# carte_pami26.net
KiCad netlist of a schematic drawn in Altium Designer
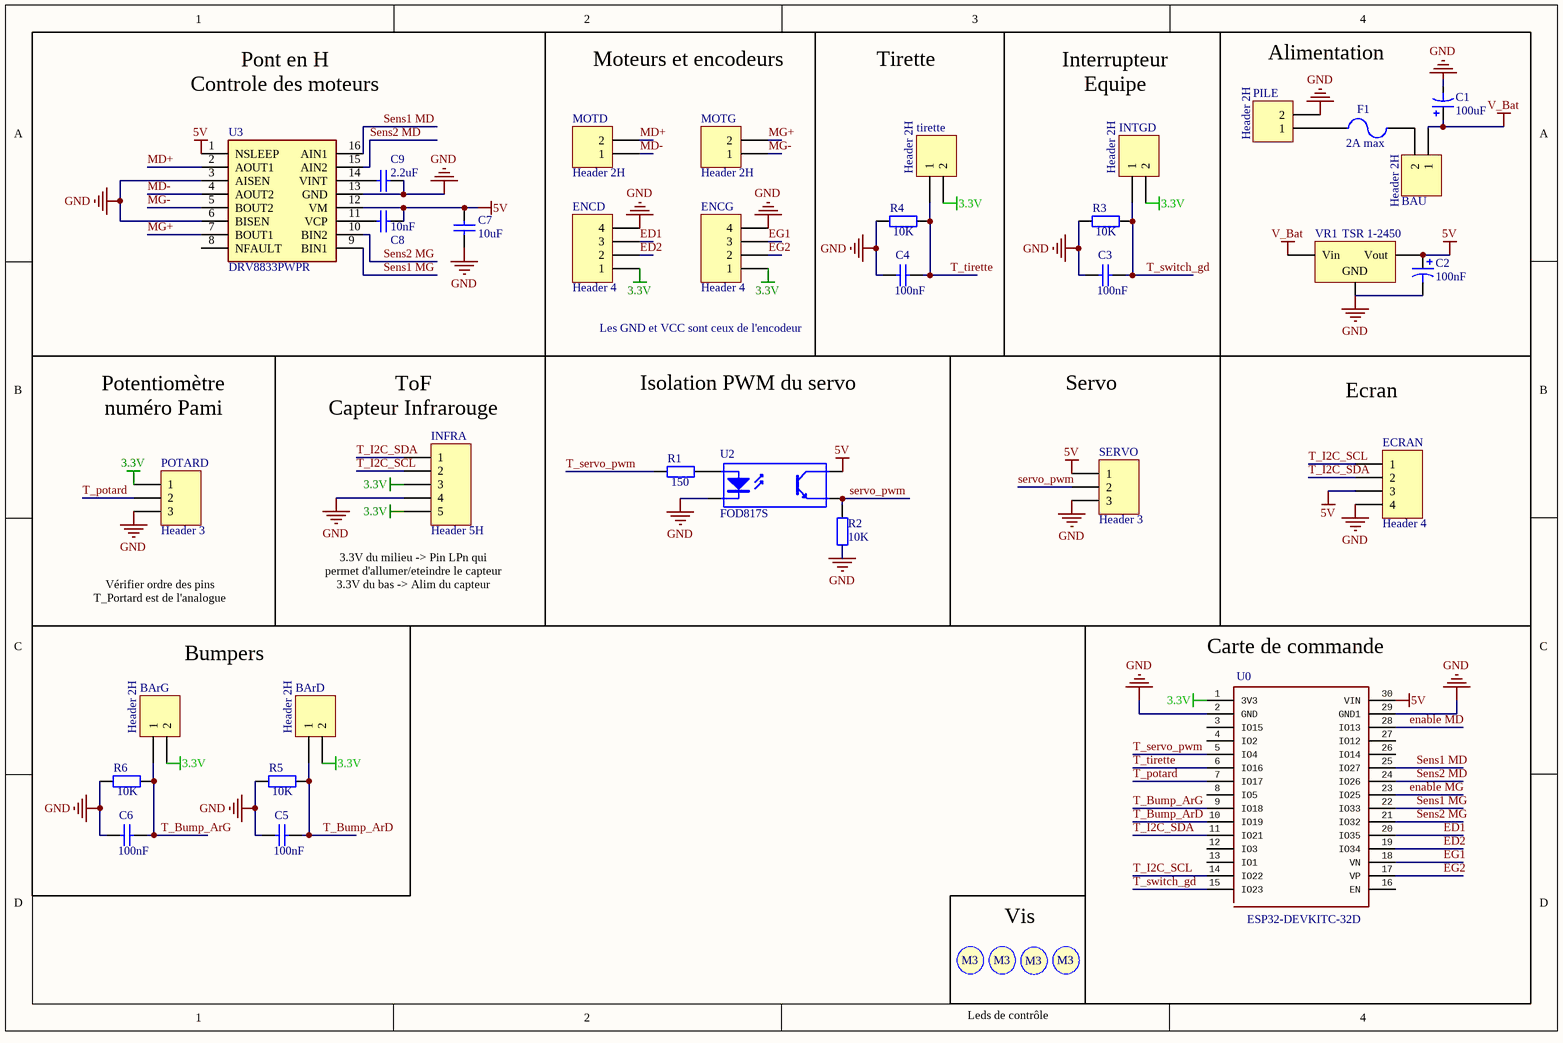
[diagram p0: carte_pami26.SchDoc]

(export (version "E")
  (design (tool "Eeschema 10.0.6"))
  (components
    (comp (ref "BArD")
      (value "Header 2H")
      (footprint "JST_B2B-XH-A_(LF)(SN)")
      (description "Header, 2-Pin, Right Angle")
      (fields (field (name "PUBLISHER") "Altium Limited"))
      (libsource (lib "Miscellaneous Connectors") (part "Header 2H"))
    )
    (comp (ref "BArG")
      (value "Header 2H")
      (footprint "JST_B2B-XH-A_(LF)(SN)")
      (description "Header, 2-Pin, Right Angle")
      (fields (field (name "PUBLISHER") "Altium Limited"))
      (libsource (lib "Miscellaneous Connectors") (part "Header 2H"))
    )
    (comp (ref "BAU")
      (value "Header 2H")
      (footprint "JST_B2B-XH-A_(LF)(SN)")
      (description "Header, 2-Pin, Right Angle")
      (fields (field (name "PUBLISHER") "Altium Limited"))
      (libsource (lib "") (part "Header 2H_1"))
    )
    (comp (ref "C1")
      (value "100uF")
      (footprint "Condensateur")
      (description "Polarized Capacitor (Radial)")
      (fields (field (name "Comment") "35V") (field (name "PUBLISHER") "Altium Limited"))
      (libsource (lib "Miscellaneous Devices") (part "Cap Pol1"))
    )
    (comp (ref "C2")
      (value "100nF")
      (footprint "Condensateur")
      (description "Polarized Capacitor (Radial)")
      (fields (field (name "Comment") "35V") (field (name "PUBLISHER") "Altium Limited"))
      (libsource (lib "Miscellaneous Devices") (part "Cap Pol1"))
    )
    (comp (ref "C3")
      (value "100nF")
      (footprint "Capacitor 1206")
      (description "Capacitor")
      (fields (field (name "Comment") "Cap") (field (name "PUBLISHER") "Altium Limited"))
      (libsource (lib "Miscellaneous Devices") (part "Cap"))
    )
    (comp (ref "C4")
      (value "100nF")
      (footprint "Capacitor 1206")
      (description "Capacitor")
      (fields (field (name "Comment") "Cap") (field (name "PUBLISHER") "Altium Limited"))
      (libsource (lib "Miscellaneous Devices") (part "Cap"))
    )
    (comp (ref "C5")
      (value "100nF")
      (footprint "Capacitor 1206")
      (description "Capacitor")
      (fields (field (name "Comment") "Cap") (field (name "PUBLISHER") "Altium Limited"))
      (libsource (lib "Miscellaneous Devices") (part "Cap"))
    )
    (comp (ref "C6")
      (value "100nF")
      (footprint "Capacitor 1206")
      (description "Capacitor")
      (fields (field (name "Comment") "Cap") (field (name "PUBLISHER") "Altium Limited"))
      (libsource (lib "Miscellaneous Devices") (part "Cap"))
    )
    (comp (ref "C7")
      (value "10uF")
      (footprint "Capacitor 1206")
      (description "Capacitor")
      (fields (field (name "Comment") "Cap") (field (name "PUBLISHER") "Altium Limited"))
      (libsource (lib "Miscellaneous Devices") (part "Cap"))
    )
    (comp (ref "C8")
      (value "10nF")
      (footprint "Capacitor 1206")
      (description "Capacitor")
      (fields (field (name "Comment") "Cap") (field (name "PUBLISHER") "Altium Limited"))
      (libsource (lib "Miscellaneous Devices") (part "Cap"))
    )
    (comp (ref "C9")
      (value "2.2uF")
      (footprint "Capacitor 1206")
      (description "Capacitor")
      (fields (field (name "Comment") "Cap") (field (name "PUBLISHER") "Altium Limited"))
      (libsource (lib "Miscellaneous Devices") (part "Cap"))
    )
    (comp (ref "ECRAN")
      (value "Header 4")
      (footprint "B4BXHALFSN")
      (description "Header, 4-Pin")
      (fields (field (name "PUBLISHER") "Altium Limited"))
      (libsource (lib "") (part "Header 4_1"))
    )
    (comp (ref "ENCD")
      (value "Header 4")
      (footprint "B4BXHALFSN")
      (description "Header, 4-Pin")
      (fields (field (name "PUBLISHER") "Altium Limited"))
      (libsource (lib "Miscellaneous Connectors") (part "Header 4"))
    )
    (comp (ref "ENCG")
      (value "Header 4")
      (footprint "B4BXHALFSN")
      (description "Header, 4-Pin")
      (fields (field (name "PUBLISHER") "Altium Limited"))
      (libsource (lib "Miscellaneous Connectors") (part "Header 4"))
    )
    (comp (ref "F1")
      (value "2A max")
      (footprint "Fuse")
      (description "Main Fuse")
      (fields (field (name "PUBLISHER") "Altium Limited"))
      (libsource (lib "Miscellaneous Devices") (part "Fuse 2"))
    )
    (comp (ref "INFRA")
      (value "Header 5H")
      (footprint "B5BXHAMLFSN")
      (description "Header, 5-Pin, Right Angle")
      (fields (field (name "PUBLISHER") "Altium Limited"))
      (libsource (lib "Miscellaneous Connectors") (part "Header 5H"))
    )
    (comp (ref "INTGD")
      (value "Header 2H")
      (footprint "JST_B2B-XH-A_(LF)(SN)")
      (description "Header, 2-Pin, Right Angle")
      (fields (field (name "PUBLISHER") "Altium Limited"))
      (libsource (lib "Miscellaneous Connectors") (part "Header 2H"))
    )
    (comp (ref "MOTD")
      (value "Header 2H")
      (footprint "JST_B2B-XH-A_(LF)(SN)")
      (description "Header, 2-Pin, Right Angle")
      (fields (field (name "PUBLISHER") "Altium Limited"))
      (libsource (lib "") (part "Header 2H_2"))
    )
    (comp (ref "MOTG")
      (value "Header 2H")
      (footprint "JST_B2B-XH-A_(LF)(SN)")
      (description "Header, 2-Pin, Right Angle")
      (fields (field (name "PUBLISHER") "Altium Limited"))
      (libsource (lib "") (part "Header 2H_2"))
    )
    (comp (ref "PILE")
      (value "Header 2H")
      (footprint "JST_B2B-XH-A_(LF)(SN)")
      (description "Header, 2-Pin, Right Angle")
      (fields (field (name "PUBLISHER") "Altium Limited"))
      (libsource (lib "") (part "Header 2H_2"))
    )
    (comp (ref "POTARD")
      (value "Header 3")
      (footprint "JST_B3B-XH-A(LF)(SN)")
      (description "Header, 3-Pin")
      (fields (field (name "PUBLISHER") "Altium Limited"))
      (libsource (lib "Miscellaneous Connectors") (part "Header 3"))
    )
    (comp (ref "R1")
      (value "150")
      (footprint "Resistor 1206")
      (description "Resistor")
      (fields (field (name "Comment") "Res2") (field (name "PUBLISHER") "Altium Limited"))
      (libsource (lib "Miscellaneous Devices") (part "Res2"))
    )
    (comp (ref "R2")
      (value "10K")
      (footprint "Resistor 1206")
      (description "Resistor")
      (fields (field (name "Comment") "Res2") (field (name "PUBLISHER") "Altium Limited"))
      (libsource (lib "") (part "Res2_1"))
    )
    (comp (ref "R3")
      (value "10K")
      (footprint "Resistor 1206")
      (description "Resistor")
      (fields (field (name "Comment") "Res2") (field (name "PUBLISHER") "Altium Limited"))
      (libsource (lib "Miscellaneous Devices") (part "Res2"))
    )
    (comp (ref "R4")
      (value "10K")
      (footprint "Resistor 1206")
      (description "Resistor")
      (fields (field (name "Comment") "Res2") (field (name "PUBLISHER") "Altium Limited"))
      (libsource (lib "Miscellaneous Devices") (part "Res2"))
    )
    (comp (ref "R5")
      (value "10K")
      (footprint "Resistor 1206")
      (description "Resistor")
      (fields (field (name "Comment") "Res2") (field (name "PUBLISHER") "Altium Limited"))
      (libsource (lib "Miscellaneous Devices") (part "Res2"))
    )
    (comp (ref "R6")
      (value "10K")
      (footprint "Resistor 1206")
      (description "Resistor")
      (fields (field (name "Comment") "Res2") (field (name "PUBLISHER") "Altium Limited"))
      (libsource (lib "Miscellaneous Devices") (part "Res2"))
    )
    (comp (ref "S1")
      (value "Screw M3")
      (footprint "Screw M3")
      (libsource (lib "Robot_2019") (part "Screw M3"))
    )
    (comp (ref "S2")
      (value "Screw M3")
      (footprint "Screw M3")
      (libsource (lib "Robot_2019") (part "Screw M3"))
    )
    (comp (ref "S3")
      (value "Screw M3")
      (footprint "Screw M3")
      (libsource (lib "Robot_2019") (part "Screw M3"))
    )
    (comp (ref "S4")
      (value "Screw M3")
      (footprint "Screw M3")
      (libsource (lib "Robot_2019") (part "Screw M3"))
    )
    (comp (ref "SERVO")
      (value "Header 3")
      (footprint "JST_B3B-XH-A(LF)(SN)")
      (description "Header, 3-Pin")
      (fields (field (name "PUBLISHER") "Altium Limited"))
      (libsource (lib "Miscellaneous Connectors") (part "Header 3"))
    )
    (comp (ref "tirette")
      (value "Header 2H")
      (footprint "JST_B2B-XH-A_(LF)(SN)")
      (description "Header, 2-Pin, Right Angle")
      (fields (field (name "PUBLISHER") "Altium Limited"))
      (libsource (lib "Miscellaneous Connectors") (part "Header 2H"))
    )
    (comp (ref "U0")
      (value "ESP32-DEVKITC-32D")
      (footprint "MODULE_ESP32-DEVKITV1")
      (description "Eval Board For Esp-Wroom-32")
      (fields (field (name "MF") "Espressif Systems"))
      (libsource (lib "AltiumLibraryDDT") (part "ESP32-DEVKITC-32D"))
    )
    (comp (ref "U2")
      (value "FOD817S")
      (footprint "SOP254P1016X385-4N")
      (description "4-Pin Phototransistor Optocoupler")
      (fields (field (name "PUBLISHER") "Altium Limited"))
      (libsource (lib "Miscellaneous Devices") (part "Optoisolator1"))
    )
    (comp (ref "U3")
      (value "DRV8833PWPR")
      (footprint "Robot_2020:SOP65P640X120-16N")
      (description "Integrated Circuit")
      (fields (field (name "MOUSER PART NUMBER") "595-DRV8833PWPR"))
      (libsource (lib "*") (part "DRV8833PWPR"))
    )
    (comp (ref "VR1")
      (value "TSR 1-2450")
      (footprint "TRS")
      (description "Voltage Regulator")
      (fields (field (name "PUBLISHER") "Altium Limited"))
      (libsource (lib "Miscellaneous Devices") (part "Volt Reg"))
    )
  )
  (nets
    (net (code "1") (name "/ED1") (class "Default")
      (node (ref "ENCD") (pin "3") (pinfunction "3_3") (pintype "passive"))
      (node (ref "U0") (pin "20") (pinfunction "IO35_20") (pintype "passive"))
    )
    (net (code "2") (name "/ED2") (class "Default")
      (node (ref "ENCD") (pin "2") (pinfunction "2_2") (pintype "passive"))
      (node (ref "U0") (pin "19") (pinfunction "IO34_19") (pintype "passive"))
    )
    (net (code "3") (name "/EG1") (class "Default")
      (node (ref "ENCG") (pin "3") (pinfunction "3_3") (pintype "passive"))
      (node (ref "U0") (pin "18") (pinfunction "VN_18") (pintype "passive"))
    )
    (net (code "4") (name "/EG2") (class "Default")
      (node (ref "ENCG") (pin "2") (pinfunction "2_2") (pintype "passive"))
      (node (ref "U0") (pin "17") (pinfunction "VP_17") (pintype "passive"))
    )
    (net (code "5") (name "/MD+") (class "Default")
      (node (ref "MOTD") (pin "2") (pinfunction "2_2") (pintype "passive"))
      (node (ref "U3") (pin "2") (pinfunction "AOUT1_2") (pintype "passive"))
    )
    (net (code "6") (name "/MD-") (class "Default")
      (node (ref "MOTD") (pin "1") (pinfunction "1_1") (pintype "passive"))
      (node (ref "U3") (pin "4") (pinfunction "AOUT2_4") (pintype "passive"))
    )
    (net (code "7") (name "/MG+") (class "Default")
      (node (ref "MOTG") (pin "2") (pinfunction "2_2") (pintype "passive"))
      (node (ref "U3") (pin "7") (pinfunction "BOUT1_7") (pintype "passive"))
    )
    (net (code "8") (name "/MG-") (class "Default")
      (node (ref "MOTG") (pin "1") (pinfunction "1_1") (pintype "passive"))
      (node (ref "U3") (pin "5") (pinfunction "BOUT2_5") (pintype "passive"))
    )
    (net (code "9") (name "/Sens1 MD") (class "Default")
      (node (ref "U0") (pin "25") (pinfunction "IO27_25") (pintype "passive"))
      (node (ref "U3") (pin "16") (pinfunction "AIN1_16") (pintype "passive"))
    )
    (net (code "10") (name "/Sens1 MG") (class "Default")
      (node (ref "U0") (pin "22") (pinfunction "IO33_22") (pintype "passive"))
      (node (ref "U3") (pin "9") (pinfunction "BIN1_9") (pintype "passive"))
    )
    (net (code "11") (name "/Sens2 MD") (class "Default")
      (node (ref "U0") (pin "24") (pinfunction "IO26_24") (pintype "passive"))
      (node (ref "U3") (pin "15") (pinfunction "AIN2_15") (pintype "passive"))
    )
    (net (code "12") (name "/Sens2 MG") (class "Default")
      (node (ref "U0") (pin "21") (pinfunction "IO32_21") (pintype "passive"))
      (node (ref "U3") (pin "10") (pinfunction "BIN2_10") (pintype "passive"))
    )
    (net (code "13") (name "/T_Bump_ArD") (class "Default")
      (node (ref "BArD") (pin "1") (pinfunction "1_1") (pintype "passive"))
      (node (ref "C5") (pin "2") (pinfunction "2_2") (pintype "passive"))
      (node (ref "R5") (pin "2") (pinfunction "2_2") (pintype "passive"))
      (node (ref "U0") (pin "10") (pinfunction "IO19_10") (pintype "passive"))
    )
    (net (code "14") (name "/T_Bump_ArG") (class "Default")
      (node (ref "BArG") (pin "1") (pinfunction "1_1") (pintype "passive"))
      (node (ref "C6") (pin "2") (pinfunction "2_2") (pintype "passive"))
      (node (ref "R6") (pin "2") (pinfunction "2_2") (pintype "passive"))
      (node (ref "U0") (pin "9") (pinfunction "IO18_9") (pintype "passive"))
    )
    (net (code "15") (name "/T_I2C_SCL") (class "Default")
      (node (ref "ECRAN") (pin "1") (pinfunction "1_1") (pintype "passive"))
      (node (ref "INFRA") (pin "2") (pinfunction "2_2") (pintype "passive"))
      (node (ref "U0") (pin "14") (pinfunction "IO22_14") (pintype "passive"))
    )
    (net (code "16") (name "/T_I2C_SDA") (class "Default")
      (node (ref "ECRAN") (pin "2") (pinfunction "2_2") (pintype "passive"))
      (node (ref "INFRA") (pin "1") (pinfunction "1_1") (pintype "passive"))
      (node (ref "U0") (pin "11") (pinfunction "IO21_11") (pintype "passive"))
    )
    (net (code "17") (name "/T_potard") (class "Default")
      (node (ref "POTARD") (pin "2") (pinfunction "2_2") (pintype "passive"))
      (node (ref "U0") (pin "7") (pinfunction "IO17_7") (pintype "passive"))
    )
    (net (code "18") (name "/T_servo_pwm") (class "Default")
      (node (ref "R1") (pin "1") (pinfunction "1_1") (pintype "passive"))
      (node (ref "U0") (pin "5") (pinfunction "IO4_5") (pintype "passive"))
    )
    (net (code "19") (name "/T_switch_gd") (class "Default")
      (node (ref "C3") (pin "2") (pinfunction "2_2") (pintype "passive"))
      (node (ref "INTGD") (pin "1") (pinfunction "1_1") (pintype "passive"))
      (node (ref "R3") (pin "2") (pinfunction "2_2") (pintype "passive"))
      (node (ref "U0") (pin "15") (pinfunction "IO23_15") (pintype "passive"))
    )
    (net (code "20") (name "/T_tirette") (class "Default")
      (node (ref "C4") (pin "2") (pinfunction "2_2") (pintype "passive"))
      (node (ref "R4") (pin "2") (pinfunction "2_2") (pintype "passive"))
      (node (ref "U0") (pin "6") (pinfunction "IO16_6") (pintype "passive"))
      (node (ref "tirette") (pin "1") (pinfunction "1_1") (pintype "passive"))
    )
    (net (code "21") (name "/enable MD") (class "Default")
      (node (ref "U0") (pin "28") (pinfunction "IO13_28") (pintype "passive"))
    )
    (net (code "22") (name "/enable MG") (class "Default")
      (node (ref "U0") (pin "23") (pinfunction "IO25_23") (pintype "passive"))
    )
    (net (code "23") (name "/servo_pwm") (class "Default")
      (node (ref "R2") (pin "2") (pinfunction "2_2") (pintype "passive"))
      (node (ref "SERVO") (pin "2") (pinfunction "2_2") (pintype "passive"))
      (node (ref "U2") (pin "3") (pinfunction "E_3") (pintype "passive"))
    )
    (net (code "24") (name "3.3V") (class "Default")
      (node (ref "BArD") (pin "2") (pinfunction "2_2") (pintype "passive"))
      (node (ref "BArG") (pin "2") (pinfunction "2_2") (pintype "passive"))
      (node (ref "ENCD") (pin "1") (pinfunction "1_1") (pintype "passive"))
      (node (ref "ENCG") (pin "1") (pinfunction "1_1") (pintype "passive"))
      (node (ref "INFRA") (pin "3") (pinfunction "3_3") (pintype "passive"))
      (node (ref "INFRA") (pin "5") (pinfunction "5_5") (pintype "passive"))
      (node (ref "INTGD") (pin "2") (pinfunction "2_2") (pintype "passive"))
      (node (ref "POTARD") (pin "1") (pinfunction "1_1") (pintype "passive"))
      (node (ref "U0") (pin "1") (pinfunction "3V3_1") (pintype "passive"))
      (node (ref "tirette") (pin "2") (pinfunction "2_2") (pintype "passive"))
    )
    (net (code "25") (name "5V") (class "Default")
      (node (ref "C2") (pin "1") (pinfunction "1_1") (pintype "passive"))
      (node (ref "C7") (pin "2") (pinfunction "2_2") (pintype "passive"))
      (node (ref "C8") (pin "1") (pinfunction "1_1") (pintype "passive"))
      (node (ref "ECRAN") (pin "3") (pinfunction "3_3") (pintype "passive"))
      (node (ref "SERVO") (pin "1") (pinfunction "1_1") (pintype "passive"))
      (node (ref "U0") (pin "30") (pinfunction "VIN_30") (pintype "passive"))
      (node (ref "U2") (pin "4") (pinfunction "C_4") (pintype "passive"))
      (node (ref "U3") (pin "1") (pinfunction "NSLEEP_1") (pintype "passive"))
      (node (ref "U3") (pin "12") (pinfunction "VM_12") (pintype "passive"))
      (node (ref "VR1") (pin "3") (pinfunction "Vout_3") (pintype "passive"))
    )
    (net (code "26") (name "GND") (class "Default")
      (node (ref "C1") (pin "2") (pinfunction "2_2") (pintype "passive"))
      (node (ref "C2") (pin "2") (pinfunction "2_2") (pintype "passive"))
      (node (ref "C3") (pin "1") (pinfunction "1_1") (pintype "passive"))
      (node (ref "C4") (pin "1") (pinfunction "1_1") (pintype "passive"))
      (node (ref "C5") (pin "1") (pinfunction "1_1") (pintype "passive"))
      (node (ref "C6") (pin "1") (pinfunction "1_1") (pintype "passive"))
      (node (ref "C7") (pin "1") (pinfunction "1_1") (pintype "passive"))
      (node (ref "C9") (pin "1") (pinfunction "1_1") (pintype "passive"))
      (node (ref "ECRAN") (pin "4") (pinfunction "4_4") (pintype "passive"))
      (node (ref "ENCD") (pin "4") (pinfunction "4_4") (pintype "passive"))
      (node (ref "ENCG") (pin "4") (pinfunction "4_4") (pintype "passive"))
      (node (ref "INFRA") (pin "4") (pinfunction "4_4") (pintype "passive"))
      (node (ref "PILE") (pin "2") (pinfunction "2_2") (pintype "passive"))
      (node (ref "POTARD") (pin "3") (pinfunction "3_3") (pintype "passive"))
      (node (ref "R2") (pin "1") (pinfunction "1_1") (pintype "passive"))
      (node (ref "R3") (pin "1") (pinfunction "1_1") (pintype "passive"))
      (node (ref "R4") (pin "1") (pinfunction "1_1") (pintype "passive"))
      (node (ref "R5") (pin "1") (pinfunction "1_1") (pintype "passive"))
      (node (ref "R6") (pin "1") (pinfunction "1_1") (pintype "passive"))
      (node (ref "SERVO") (pin "3") (pinfunction "3_3") (pintype "passive"))
      (node (ref "U0") (pin "2") (pinfunction "GND_2") (pintype "passive"))
      (node (ref "U0") (pin "29") (pinfunction "GND1_29") (pintype "passive"))
      (node (ref "U2") (pin "2") (pinfunction "K_2") (pintype "passive"))
      (node (ref "U3") (pin "13") (pinfunction "GND_13") (pintype "passive"))
      (node (ref "U3") (pin "3") (pinfunction "AISEN_3") (pintype "passive"))
      (node (ref "U3") (pin "6") (pinfunction "BISEN_6") (pintype "passive"))
    )
    (net (code "27") (name "Net-(BAU-Pad2)") (class "Default")
      (node (ref "BAU") (pin "2") (pinfunction "2_2") (pintype "passive"))
      (node (ref "F1") (pin "1") (pinfunction "1_1") (pintype "passive"))
    )
    (net (code "28") (name "Net-(F1-Pad2)") (class "Default")
      (node (ref "F1") (pin "2") (pinfunction "2_2") (pintype "passive"))
      (node (ref "PILE") (pin "1") (pinfunction "1_1") (pintype "passive"))
    )
    (net (code "29") (name "Net-(U2-A)") (class "Default")
      (node (ref "R1") (pin "2") (pinfunction "2_2") (pintype "passive"))
      (node (ref "U2") (pin "1") (pinfunction "A_1") (pintype "passive"))
    )
    (net (code "30") (name "Net-(U3-VCP)") (class "Default")
      (node (ref "C8") (pin "2") (pinfunction "2_2") (pintype "passive"))
      (node (ref "U3") (pin "11") (pinfunction "VCP_11") (pintype "passive"))
    )
    (net (code "31") (name "Net-(U3-VINT)") (class "Default")
      (node (ref "C9") (pin "2") (pinfunction "2_2") (pintype "passive"))
      (node (ref "U3") (pin "14") (pinfunction "VINT_14") (pintype "passive"))
    )
    (net (code "32") (name "V_Bat") (class "Default")
      (node (ref "BAU") (pin "1") (pinfunction "1_1") (pintype "passive"))
      (node (ref "C1") (pin "1") (pinfunction "1_1") (pintype "passive"))
      (node (ref "VR1") (pin "1") (pinfunction "Vin_1") (pintype "passive"))
    )
    (net (code "33") (name "unconnected-(U0-EN-Pad16)") (class "Default")
      (node (ref "U0") (pin "16") (pinfunction "EN_16") (pintype "passive"))
    )
    (net (code "34") (name "unconnected-(U0-IO1-Pad13)") (class "Default")
      (node (ref "U0") (pin "13") (pinfunction "IO1_13") (pintype "passive"))
    )
    (net (code "35") (name "unconnected-(U0-IO2-Pad4)") (class "Default")
      (node (ref "U0") (pin "4") (pinfunction "IO2_4") (pintype "passive"))
    )
    (net (code "36") (name "unconnected-(U0-IO3-Pad12)") (class "Default")
      (node (ref "U0") (pin "12") (pinfunction "IO3_12") (pintype "passive"))
    )
    (net (code "37") (name "unconnected-(U0-IO5-Pad8)") (class "Default")
      (node (ref "U0") (pin "8") (pinfunction "IO5_8") (pintype "passive"))
    )
    (net (code "38") (name "unconnected-(U0-IO12-Pad27)") (class "Default")
      (node (ref "U0") (pin "27") (pinfunction "IO12_27") (pintype "passive"))
    )
    (net (code "39") (name "unconnected-(U0-IO14-Pad26)") (class "Default")
      (node (ref "U0") (pin "26") (pinfunction "IO14_26") (pintype "passive"))
    )
    (net (code "40") (name "unconnected-(U0-IO15-Pad3)") (class "Default")
      (node (ref "U0") (pin "3") (pinfunction "IO15_3") (pintype "passive"))
    )
    (net (code "41") (name "unconnected-(U3-NFAULT-Pad8)") (class "Default")
      (node (ref "U3") (pin "8") (pinfunction "NFAULT_8") (pintype "passive"))
    )
    (net (code "42") (name "unconnected-(VR1-GND-Pad2)") (class "Default")
      (node (ref "VR1") (pin "2") (pinfunction "GND_2") (pintype "passive"))
    )
  )
)
